# SM2.net
KiCad netlist of a schematic drawn in Altium Designer
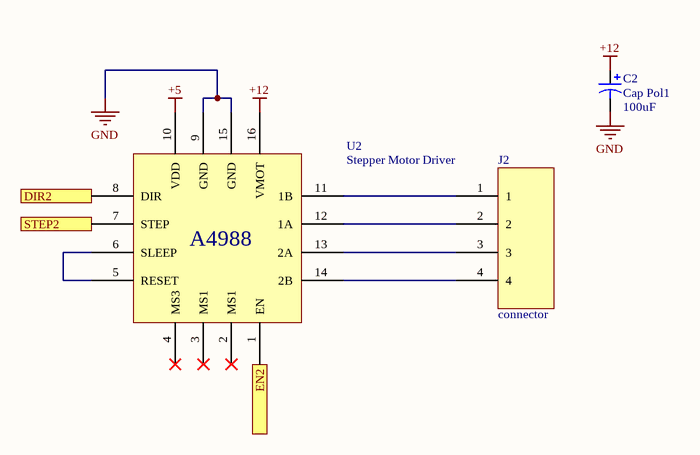
[diagram p0: SM2.SchDoc]

(export (version "E")
  (design (tool "Eeschema 10.0.6"))
  (components
    (comp (ref "C2")
      (value "Cap Pol1")
      (footprint "RB7.6-15")
      (description "Polarized Capacitor (Radial)")
      (fields (field (name "ALTIUM_VALUE") "100uF") (field (name "PUBLISHER") "Altium Limited"))
      (libsource (lib "Miscellaneous Devices") (part "Cap Pol1"))
    )
    (comp (ref "J2") (value "connector") (libsource (lib "Schlib") (part "JST_4P")))
    (comp (ref "U2") (value "Stepper Motor Driver") (libsource (lib "Schlib") (part "A4988")))
  )
  (nets
    (net (code "1") (name "+5") (class "Default")
      (node (ref "U2") (pin "10") (pinfunction "VDD_10") (pintype "passive"))
    )
    (net (code "2") (name "+12") (class "Default")
      (node (ref "C2") (pin "1") (pinfunction "1_1") (pintype "passive"))
      (node (ref "U2") (pin "16") (pinfunction "VMOT_16") (pintype "passive"))
    )
    (net (code "3") (name "/DIR2") (class "Default")
      (node (ref "U2") (pin "8") (pinfunction "DIR_8") (pintype "passive"))
    )
    (net (code "4") (name "/EN2") (class "Default")
      (node (ref "U2") (pin "1") (pinfunction "EN_1") (pintype "passive"))
    )
    (net (code "5") (name "/STEP2") (class "Default")
      (node (ref "U2") (pin "7") (pinfunction "STEP_7") (pintype "passive"))
    )
    (net (code "6") (name "GND") (class "Default")
      (node (ref "C2") (pin "2") (pinfunction "2_2") (pintype "passive"))
      (node (ref "U2") (pin "15") (pinfunction "GND_15") (pintype "passive"))
      (node (ref "U2") (pin "9") (pinfunction "GND_9") (pintype "passive"))
    )
    (net (code "7") (name "Net-(U2-1A)") (class "Default")
      (node (ref "J2") (pin "2") (pinfunction "2_2") (pintype "passive"))
      (node (ref "U2") (pin "12") (pinfunction "1A_12") (pintype "passive"))
    )
    (net (code "8") (name "Net-(U2-1B)") (class "Default")
      (node (ref "J2") (pin "1") (pinfunction "1_1") (pintype "passive"))
      (node (ref "U2") (pin "11") (pinfunction "1B_11") (pintype "passive"))
    )
    (net (code "9") (name "Net-(U2-2A)") (class "Default")
      (node (ref "J2") (pin "3") (pinfunction "3_3") (pintype "passive"))
      (node (ref "U2") (pin "13") (pinfunction "2A_13") (pintype "passive"))
    )
    (net (code "10") (name "Net-(U2-2B)") (class "Default")
      (node (ref "J2") (pin "4") (pinfunction "4_4") (pintype "passive"))
      (node (ref "U2") (pin "14") (pinfunction "2B_14") (pintype "passive"))
    )
    (net (code "11") (name "Net-(U2-RESET)") (class "Default")
      (node (ref "U2") (pin "5") (pinfunction "RESET_5") (pintype "passive"))
      (node (ref "U2") (pin "6") (pinfunction "SLEEP_6") (pintype "passive"))
    )
    (net (code "12") (name "unconnected-(U2-MS1-Pad2)") (class "Default")
      (node (ref "U2") (pin "2") (pinfunction "MS1_2") (pintype "passive+no_connect"))
    )
    (net (code "13") (name "unconnected-(U2-MS1-Pad3)") (class "Default")
      (node (ref "U2") (pin "3") (pinfunction "MS1_3") (pintype "passive+no_connect"))
    )
    (net (code "14") (name "unconnected-(U2-MS3-Pad4)") (class "Default")
      (node (ref "U2") (pin "4") (pinfunction "MS3_4") (pintype "passive+no_connect"))
    )
  )
)
